# Temp.net
KiCad netlist of a schematic drawn in Altium Designer
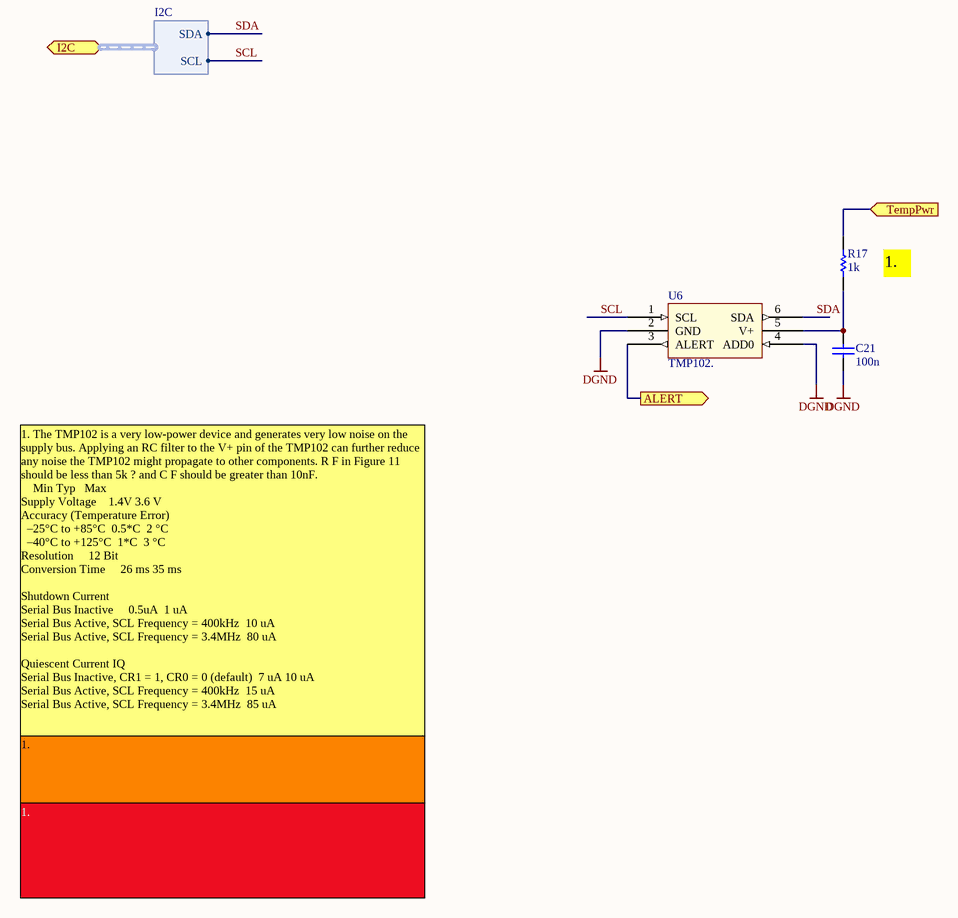
[diagram p0: Temp.SchDoc]

(export (version "E")
  (design (tool "Eeschema 10.0.6"))
  (components
    (comp (ref "C21")
      (value "100n")
      (footprint "CC-0402-AL")
      (description "Capacitor (Semiconductor SIM Model)")
      (fields (field (name "Comment") "Cap Semi"))
      (libsource (lib "Z1_Project") (part "Cap Semi"))
    )
    (comp (ref "R17")
      (value "1k")
      (footprint "CR-0402-AL")
      (description "Semiconductor Resistor")
      (fields (field (name "MANUFACTURER") "Generic Components") (field (name "Comment") "Res Semi"))
      (libsource (lib "Z1_Project") (part "Res Semi"))
    )
    (comp (ref "U6")
      (value "TMP102.")
      (footprint "SOT-TMP102")
      (libsource (lib "Z1_Project") (part "TMP102"))
    )
  )
  (nets
    (net (code "2") (name "/ALERT") (class "Default")
      (node (ref "U6") (pin "3") (pinfunction "ALERT_3") (pintype "output"))
    )
    (net (code "3") (name "/SCL") (class "Default")
      (node (ref "U6") (pin "1") (pinfunction "SCL_1") (pintype "input"))
    )
    (net (code "4") (name "/SDA") (class "Default")
      (node (ref "U6") (pin "6") (pinfunction "SDA_6") (pintype "output"))
    )
    (net (code "5") (name "/TempPwr") (class "Default")
      (node (ref "R17") (pin "2") (pinfunction "2_2") (pintype "passive"))
    )
    (net (code "7") (name "DGND") (class "Default")
      (node (ref "C21") (pin "2") (pinfunction "2_2") (pintype "passive"))
      (node (ref "U6") (pin "2") (pinfunction "GND_2") (pintype "power_in"))
      (node (ref "U6") (pin "4") (pinfunction "ADD0_4") (pintype "input"))
    )
    (net (code "8") (name "Net-(U6-V+)") (class "Default")
      (node (ref "C21") (pin "1") (pinfunction "1_1") (pintype "passive"))
      (node (ref "R17") (pin "1") (pinfunction "1_1") (pintype "passive"))
      (node (ref "U6") (pin "5") (pinfunction "V+_5") (pintype "power_in"))
    )
  )
)
